# charger_v4.net
KiCad netlist of a schematic drawn in EAGLE
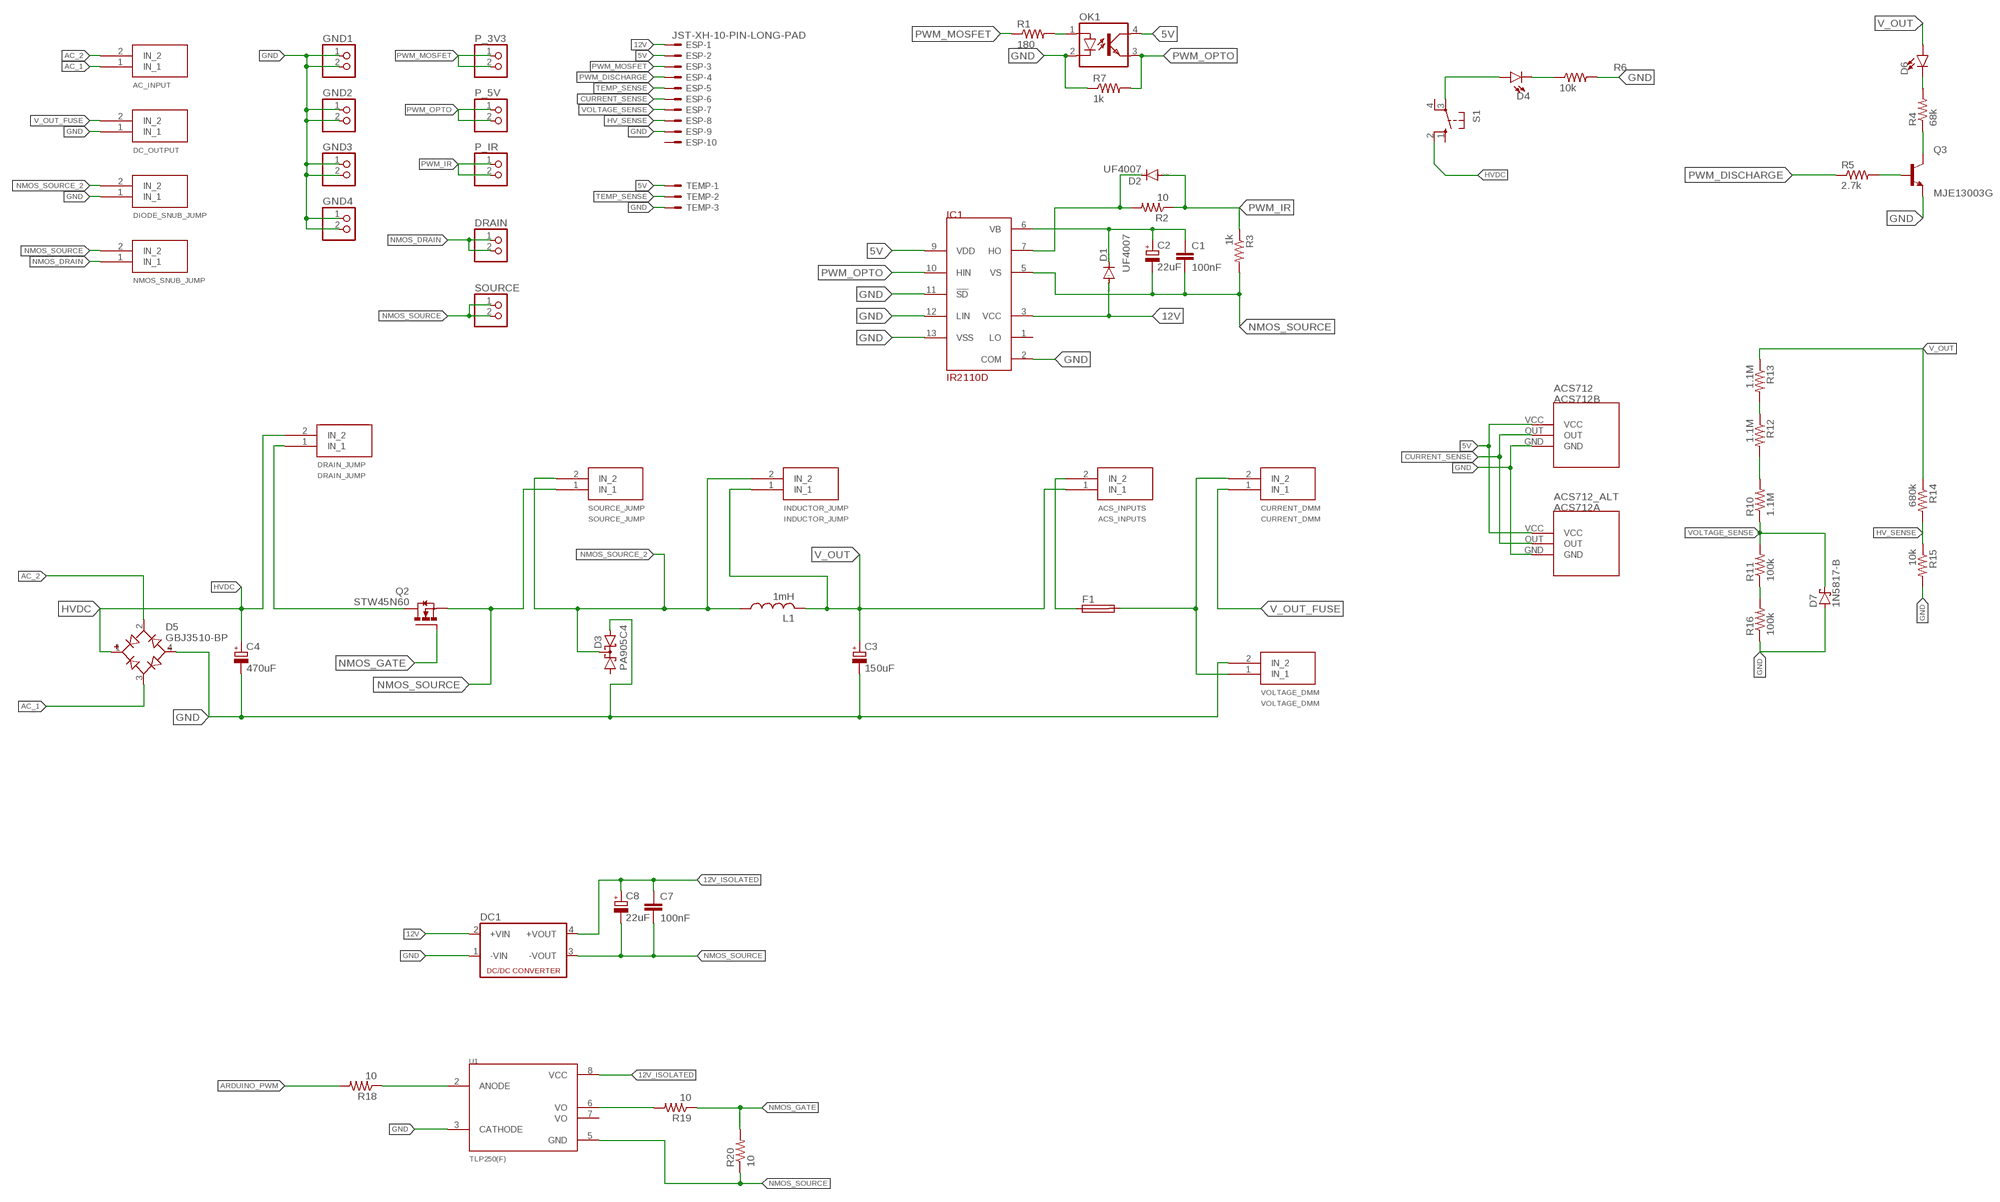
[diagram p0: schematic, sheet 1]

(export (version "E")
  (design (tool "Eeschema 10.0.6"))
  (components
    (comp (ref "ACS712")
      (value "ACS712B")
      (footprint "eagle-import:ACS712-2")
      (libsource (lib "eagle-import") (part "ACS712B"))
    )
    (comp (ref "ACS712_ALT")
      (value "ACS712A")
      (footprint "eagle-import:ACS712-1")
      (libsource (lib "eagle-import") (part "ACS712A"))
    )
    (comp (ref "ACS_INPUTS")
      (value "ACS_INPUTS")
      (footprint "eagle-import:TERMINAL_2P")
      (libsource (lib "eagle-import") (part "TERMINAL_2P"))
    )
    (comp (ref "AC_INPUT")
      (value "AC_INPUT")
      (footprint "eagle-import:TERMINAL_2P")
      (libsource (lib "eagle-import") (part "TERMINAL_2P"))
    )
    (comp (ref "C1")
      (value "100nF")
      (footprint "eagle-import:C025-025X050")
      (libsource (lib "eagle-import") (part "C-EU025-025X050"))
    )
    (comp (ref "C2")
      (value "22uF")
      (footprint "eagle-import:E2,5-6E")
      (libsource (lib "eagle-import") (part "CPOL-EUE2,5-6E"))
    )
    (comp (ref "C3")
      (value "150uF")
      (footprint "eagle-import:E7,5-18")
      (libsource (lib "eagle-import") (part "CPOL-EUE7.5-18"))
    )
    (comp (ref "C4")
      (value "470uF")
      (footprint "eagle-import:EB35D")
      (libsource (lib "eagle-import") (part "CPOL-EUE10-35"))
    )
    (comp (ref "C7")
      (value "100nF")
      (footprint "eagle-import:C025-025X050")
      (libsource (lib "eagle-import") (part "C-EU025-025X050"))
    )
    (comp (ref "C8")
      (value "22uF")
      (footprint "eagle-import:E2,5-6E")
      (libsource (lib "eagle-import") (part "CPOL-EUE2,5-6E"))
    )
    (comp (ref "CURRENT_DMM")
      (value "CURRENT_DMM")
      (footprint "eagle-import:TERMINAL_2P")
      (libsource (lib "eagle-import") (part "TERMINAL_2P"))
    )
    (comp (ref "D1")
      (value "UF4007")
      (footprint "eagle-import:DO34-7")
      (libsource (lib "eagle-import") (part "BAS15"))
    )
    (comp (ref "D2")
      (value "UF4007")
      (footprint "eagle-import:DO34-7")
      (libsource (lib "eagle-import") (part "BAS15"))
    )
    (comp (ref "D3")
      (value "PA905C4")
      (footprint "eagle-import:SOT93S")
      (libsource (lib "eagle-import") (part "PBYR3035"))
    )
    (comp (ref "D4")
      (value "LED5MM")
      (footprint "eagle-import:LED_5MM")
      (libsource (lib "eagle-import") (part "LED5MM"))
    )
    (comp (ref "D5")
      (value "GBJ3510-BP")
      (footprint "eagle-import:DIOB_GBJ3510-BP")
      (fields (field (name "MF") "Micro Commercial"))
      (libsource (lib "eagle-import") (part "GBJ3510-BP"))
    )
    (comp (ref "D6")
      (value "LED5MM")
      (footprint "eagle-import:LED_5MM")
      (libsource (lib "eagle-import") (part "LED5MM"))
    )
    (comp (ref "D7")
      (value "1N5817-B")
      (footprint "eagle-import:DO41-7.6")
      (libsource (lib "eagle-import") (part "1N5817-B"))
    )
    (comp (ref "DC1")
      (value "NME")
      (footprint "eagle-import:NME")
      (fields (field (name "MF") "C & D TECHNOLOGIES, INC") (field (name "MPN") "NME1205D"))
      (libsource (lib "eagle-import") (part "NME"))
    )
    (comp (ref "DC_OUTPUT")
      (value "DC_OUTPUT")
      (footprint "eagle-import:TERMINAL_2P")
      (libsource (lib "eagle-import") (part "TERMINAL_2P"))
    )
    (comp (ref "DIODE_SNUB_JUMP")
      (value "DIODE_SNUB_JUMP")
      (footprint "eagle-import:TERMINAL_2P")
      (libsource (lib "eagle-import") (part "TERMINAL_2P"))
    )
    (comp (ref "DRAIN")
      (value "PINHD-1X2")
      (footprint "eagle-import:1X02")
      (libsource (lib "eagle-import") (part "PINHD-1X2"))
    )
    (comp (ref "DRAIN_JUMP")
      (value "DRAIN_JUMP")
      (footprint "eagle-import:TERMINAL_2P")
      (libsource (lib "eagle-import") (part "TERMINAL_2P"))
    )
    (comp (ref "ESP")
      (value "JST-XH-10-PIN-LONG-PAD")
      (footprint "eagle-import:JST-XH-10-PACKAGE-LONG-PAD")
      (libsource (lib "eagle-import") (part "JST-XH-10-PIN-LONG-PAD"))
    )
    (comp (ref "F1")
      (value "FUSEHOLDER")
      (footprint "eagle-import:FUSEHOLDER")
      (fields (field (name "MPN") "0031.7701.11"))
      (libsource (lib "eagle-import") (part "FUSEHOLDER"))
    )
    (comp (ref "GND1")
      (value "PINHD-1X2")
      (footprint "eagle-import:1X02")
      (libsource (lib "eagle-import") (part "PINHD-1X2"))
    )
    (comp (ref "GND2")
      (value "PINHD-1X2")
      (footprint "eagle-import:1X02")
      (libsource (lib "eagle-import") (part "PINHD-1X2"))
    )
    (comp (ref "GND3")
      (value "PINHD-1X2")
      (footprint "eagle-import:1X02")
      (libsource (lib "eagle-import") (part "PINHD-1X2"))
    )
    (comp (ref "GND4")
      (value "PINHD-1X2")
      (footprint "eagle-import:1X02")
      (libsource (lib "eagle-import") (part "PINHD-1X2"))
    )
    (comp (ref "IC1")
      (value "IR2110D")
      (footprint "eagle-import:DIL14")
      (libsource (lib "eagle-import") (part "IR2110D"))
    )
    (comp (ref "INDUCTOR_JUMP")
      (value "INDUCTOR_JUMP")
      (footprint "eagle-import:TERMINAL_2P")
      (libsource (lib "eagle-import") (part "TERMINAL_2P"))
    )
    (comp (ref "L1")
      (value "1mH")
      (footprint "eagle-import:TJ7-U1")
      (libsource (lib "eagle-import") (part "L-USTJ7-U1"))
    )
    (comp (ref "NMOS_SNUB_JUMP")
      (value "NMOS_SNUB_JUMP")
      (footprint "eagle-import:TERMINAL_2P")
      (libsource (lib "eagle-import") (part "TERMINAL_2P"))
    )
    (comp (ref "OK1")
      (value "SFH618A-5")
      (footprint "eagle-import:DIP4")
      (fields (field (name "MF") "VISHAY/TELEFUNKEN"))
      (libsource (lib "eagle-import") (part "SFH618?A-5"))
    )
    (comp (ref "P_3V3")
      (value "PINHD-1X2")
      (footprint "eagle-import:1X02")
      (libsource (lib "eagle-import") (part "PINHD-1X2"))
    )
    (comp (ref "P_5V")
      (value "PINHD-1X2")
      (footprint "eagle-import:1X02")
      (libsource (lib "eagle-import") (part "PINHD-1X2"))
    )
    (comp (ref "P_IR")
      (value "PINHD-1X2")
      (footprint "eagle-import:1X02")
      (libsource (lib "eagle-import") (part "PINHD-1X2"))
    )
    (comp (ref "Q2")
      (value "STW45N60")
      (footprint "eagle-import:TO247AC")
      (fields (field (name "MF") "Vishay Siliconix") (field (name "MP") "IRFP240"))
      (libsource (lib "eagle-import") (part "IRFP240"))
    )
    (comp (ref "Q3")
      (value "MJE13003G")
      (footprint "eagle-import:TO229P780X300X1364-3")
      (fields (field (name "MF") "ON Semiconductor"))
      (libsource (lib "eagle-import") (part "MJE13003G"))
    )
    (comp (ref "R1")
      (value "180")
      (footprint "eagle-import:0204_7")
      (libsource (lib "eagle-import") (part "R-US_0204/7"))
    )
    (comp (ref "R2")
      (value "10")
      (footprint "eagle-import:0204_7")
      (libsource (lib "eagle-import") (part "R-US_0204/7"))
    )
    (comp (ref "R3")
      (value "1k")
      (footprint "eagle-import:0204_7")
      (libsource (lib "eagle-import") (part "R-US_0204/7"))
    )
    (comp (ref "R4")
      (value "68k")
      (footprint "eagle-import:0411_15")
      (libsource (lib "eagle-import") (part "R-US_0411/15"))
    )
    (comp (ref "R5")
      (value "2.7k")
      (footprint "eagle-import:0204_7")
      (libsource (lib "eagle-import") (part "R-US_0204/7"))
    )
    (comp (ref "R6")
      (value "10k")
      (footprint "eagle-import:0204_7")
      (libsource (lib "eagle-import") (part "R-US_0204/7"))
    )
    (comp (ref "R7")
      (value "1k")
      (footprint "eagle-import:0204_7")
      (libsource (lib "eagle-import") (part "R-US_0204/7"))
    )
    (comp (ref "R10")
      (value "1.1M")
      (footprint "eagle-import:R0805")
      (libsource (lib "eagle-import") (part "R-US_R0805"))
    )
    (comp (ref "R11")
      (value "100k")
      (footprint "eagle-import:R0805")
      (libsource (lib "eagle-import") (part "R-US_R0805"))
    )
    (comp (ref "R12")
      (value "1.1M")
      (footprint "eagle-import:R0805")
      (libsource (lib "eagle-import") (part "R-US_R0805"))
    )
    (comp (ref "R13")
      (value "1.1M")
      (footprint "eagle-import:R0805")
      (libsource (lib "eagle-import") (part "R-US_R0805"))
    )
    (comp (ref "R14")
      (value "680k")
      (footprint "eagle-import:0207_10")
      (libsource (lib "eagle-import") (part "R-US_0207/10"))
    )
    (comp (ref "R15")
      (value "10k")
      (footprint "eagle-import:0207_10")
      (libsource (lib "eagle-import") (part "R-US_0207/10"))
    )
    (comp (ref "R16")
      (value "100k")
      (footprint "eagle-import:R0805")
      (libsource (lib "eagle-import") (part "R-US_R0805"))
    )
    (comp (ref "R18")
      (value "10")
      (footprint "eagle-import:0204_7")
      (libsource (lib "eagle-import") (part "R-US_0204/7"))
    )
    (comp (ref "R19")
      (value "10")
      (footprint "eagle-import:0204_7")
      (libsource (lib "eagle-import") (part "R-US_0204/7"))
    )
    (comp (ref "R20")
      (value "10")
      (footprint "eagle-import:0204_7")
      (libsource (lib "eagle-import") (part "R-US_0204/7"))
    )
    (comp (ref "S1")
      (value "10-XX")
      (footprint "eagle-import:B3F-10XX")
      (fields (field (name "MPN") "B3F-1000"))
      (libsource (lib "eagle-import") (part "10-XX"))
    )
    (comp (ref "SOURCE")
      (value "PINHD-1X2")
      (footprint "eagle-import:1X02")
      (libsource (lib "eagle-import") (part "PINHD-1X2"))
    )
    (comp (ref "SOURCE_JUMP")
      (value "SOURCE_JUMP")
      (footprint "eagle-import:TERMINAL_2P")
      (libsource (lib "eagle-import") (part "TERMINAL_2P"))
    )
    (comp (ref "TEMP")
      (value "JST-XH-03-PIN-LONG-PAD")
      (footprint "eagle-import:JST-XH-03-PACKAGE-LONG-PAD")
      (libsource (lib "eagle-import") (part "JST-XH-03-PIN-LONG-PAD"))
    )
    (comp (ref "U1")
      (value "TLP250(F)")
      (footprint "eagle-import:DIP1016W50P254L966H380Q8P")
      (fields (field (name "MF") "Toshiba"))
      (libsource (lib "eagle-import") (part "TLP250(F)"))
    )
    (comp (ref "VOLTAGE_DMM")
      (value "VOLTAGE_DMM")
      (footprint "eagle-import:TERMINAL_2P")
      (libsource (lib "eagle-import") (part "TERMINAL_2P"))
    )
  )
  (nets
    (net (code "1") (name "5V") (class "Default")
      (node (ref "ACS712") (pin "VCC") (pinfunction "VCC_VCC") (pintype "bidirectional"))
      (node (ref "ACS712_ALT") (pin "VCC") (pinfunction "VCC_VCC") (pintype "bidirectional"))
      (node (ref "ESP") (pin "2") (pinfunction "S_2") (pintype "passive"))
      (node (ref "IC1") (pin "9") (pinfunction "VDD_9") (pintype "power_in"))
      (node (ref "OK1") (pin "4") (pinfunction "COL_4") (pintype "passive"))
      (node (ref "TEMP") (pin "1") (pinfunction "S_1") (pintype "passive"))
    )
    (net (code "2") (name "12V") (class "Default")
      (node (ref "D1") (pin "A") (pinfunction "A_A") (pintype "passive"))
      (node (ref "DC1") (pin "2") (pinfunction "+VIN_2") (pintype "passive"))
      (node (ref "ESP") (pin "1") (pinfunction "S_1") (pintype "passive"))
      (node (ref "IC1") (pin "3") (pinfunction "VCC_3") (pintype "power_in"))
    )
    (net (code "3") (name "12V_ISOLATED") (class "Default")
      (node (ref "C7") (pin "1") (pinfunction "1_1") (pintype "passive"))
      (node (ref "C8") (pin "+") (pinfunction "+_+") (pintype "passive"))
      (node (ref "DC1") (pin "4") (pinfunction "+VOUT_4") (pintype "passive"))
      (node (ref "U1") (pin "8") (pinfunction "VCC_8") (pintype "power_in"))
    )
    (net (code "4") (name "AC_1") (class "Default")
      (node (ref "AC_INPUT") (pin "1") (pinfunction "IN_1_1") (pintype "bidirectional"))
      (node (ref "D5") (pin "3") (pinfunction "AC2_3") (pintype "passive"))
    )
    (net (code "5") (name "AC_2") (class "Default")
      (node (ref "AC_INPUT") (pin "2") (pinfunction "IN_2_2") (pintype "bidirectional"))
      (node (ref "D5") (pin "2") (pinfunction "AC1_2") (pintype "passive"))
    )
    (net (code "6") (name "ARDUINO_PWM") (class "Default")
      (node (ref "R18") (pin "2") (pinfunction "2_2") (pintype "passive"))
    )
    (net (code "7") (name "CURRENT_SENSE") (class "Default")
      (node (ref "ACS712") (pin "OUT") (pinfunction "OUT_OUT") (pintype "bidirectional"))
      (node (ref "ACS712_ALT") (pin "OUT") (pinfunction "OUT_OUT") (pintype "bidirectional"))
      (node (ref "ESP") (pin "6") (pinfunction "S_6") (pintype "passive"))
    )
    (net (code "8") (name "GND") (class "Default")
      (node (ref "ACS712") (pin "GND") (pinfunction "GND_GND") (pintype "bidirectional"))
      (node (ref "ACS712_ALT") (pin "GND") (pinfunction "GND_GND") (pintype "bidirectional"))
      (node (ref "C3") (pin "-") (pinfunction "-_-") (pintype "passive"))
      (node (ref "C4") (pin "-") (pinfunction "-_-") (pintype "passive"))
      (node (ref "D3") (pin "A2") (pinfunction "A2_A2") (pintype "passive"))
      (node (ref "D5") (pin "4") (pinfunction "-_4") (pintype "passive"))
      (node (ref "D7") (pin "A") (pinfunction "A_A") (pintype "passive"))
      (node (ref "DC1") (pin "1") (pinfunction "-VIN_1") (pintype "passive"))
      (node (ref "DC_OUTPUT") (pin "1") (pinfunction "IN_1_1") (pintype "bidirectional"))
      (node (ref "DIODE_SNUB_JUMP") (pin "1") (pinfunction "IN_1_1") (pintype "bidirectional"))
      (node (ref "ESP") (pin "9") (pinfunction "S_9") (pintype "passive"))
      (node (ref "GND1") (pin "1") (pinfunction "1_1") (pintype "passive"))
      (node (ref "GND1") (pin "2") (pinfunction "2_2") (pintype "passive"))
      (node (ref "GND2") (pin "1") (pinfunction "1_1") (pintype "passive"))
      (node (ref "GND2") (pin "2") (pinfunction "2_2") (pintype "passive"))
      (node (ref "GND3") (pin "1") (pinfunction "1_1") (pintype "passive"))
      (node (ref "GND3") (pin "2") (pinfunction "2_2") (pintype "passive"))
      (node (ref "GND4") (pin "1") (pinfunction "1_1") (pintype "passive"))
      (node (ref "GND4") (pin "2") (pinfunction "2_2") (pintype "passive"))
      (node (ref "IC1") (pin "11") (pinfunction "~{SD}_11") (pintype "input"))
      (node (ref "IC1") (pin "12") (pinfunction "LIN_12") (pintype "input"))
      (node (ref "IC1") (pin "13") (pinfunction "VSS_13") (pintype "power_in"))
      (node (ref "IC1") (pin "2") (pinfunction "COM_2") (pintype "power_in"))
      (node (ref "OK1") (pin "2") (pinfunction "C_2") (pintype "passive"))
      (node (ref "Q3") (pin "3") (pinfunction "E_3") (pintype "passive"))
      (node (ref "R15") (pin "2") (pinfunction "2_2") (pintype "passive"))
      (node (ref "R16") (pin "1") (pinfunction "1_1") (pintype "passive"))
      (node (ref "R6") (pin "2") (pinfunction "2_2") (pintype "passive"))
      (node (ref "R7") (pin "1") (pinfunction "1_1") (pintype "passive"))
      (node (ref "TEMP") (pin "3") (pinfunction "S_3") (pintype "passive"))
      (node (ref "U1") (pin "3") (pinfunction "CATHODE_3") (pintype "passive"))
      (node (ref "VOLTAGE_DMM") (pin "2") (pinfunction "IN_2_2") (pintype "bidirectional"))
    )
    (net (code "9") (name "HVDC") (class "Default")
      (node (ref "C4") (pin "+") (pinfunction "+_+") (pintype "passive"))
      (node (ref "D5") (pin "1") (pinfunction "+_1") (pintype "passive"))
      (node (ref "DRAIN_JUMP") (pin "2") (pinfunction "IN_2_2") (pintype "bidirectional"))
      (node (ref "S1") (pin "2") (pinfunction "S1_2") (pintype "passive"))
    )
    (net (code "10") (name "HV_SENSE") (class "Default")
      (node (ref "ESP") (pin "8") (pinfunction "S_8") (pintype "passive"))
      (node (ref "R14") (pin "2") (pinfunction "2_2") (pintype "passive"))
      (node (ref "R15") (pin "1") (pinfunction "1_1") (pintype "passive"))
    )
    (net (code "11") (name "NMOS_DRAIN") (class "Default")
      (node (ref "DRAIN") (pin "1") (pinfunction "1_1") (pintype "passive"))
      (node (ref "DRAIN") (pin "2") (pinfunction "2_2") (pintype "passive"))
      (node (ref "DRAIN_JUMP") (pin "1") (pinfunction "IN_1_1") (pintype "bidirectional"))
      (node (ref "NMOS_SNUB_JUMP") (pin "1") (pinfunction "IN_1_1") (pintype "bidirectional"))
      (node (ref "Q2") (pin "2") (pinfunction "D_2") (pintype "passive"))
    )
    (net (code "12") (name "NMOS_GATE") (class "Default")
      (node (ref "Q2") (pin "1") (pinfunction "G_1") (pintype "passive"))
      (node (ref "R19") (pin "1") (pinfunction "1_1") (pintype "passive"))
      (node (ref "R20") (pin "2") (pinfunction "2_2") (pintype "passive"))
    )
    (net (code "13") (name "NMOS_SOURCE") (class "Default")
      (node (ref "C1") (pin "2") (pinfunction "2_2") (pintype "passive"))
      (node (ref "C2") (pin "-") (pinfunction "-_-") (pintype "passive"))
      (node (ref "C7") (pin "2") (pinfunction "2_2") (pintype "passive"))
      (node (ref "C8") (pin "-") (pinfunction "-_-") (pintype "passive"))
      (node (ref "DC1") (pin "3") (pinfunction "-VOUT_3") (pintype "passive"))
      (node (ref "IC1") (pin "5") (pinfunction "VS_5") (pintype "power_in"))
      (node (ref "NMOS_SNUB_JUMP") (pin "2") (pinfunction "IN_2_2") (pintype "bidirectional"))
      (node (ref "Q2") (pin "3") (pinfunction "S_3") (pintype "passive"))
      (node (ref "R20") (pin "1") (pinfunction "1_1") (pintype "passive"))
      (node (ref "R3") (pin "2") (pinfunction "2_2") (pintype "passive"))
      (node (ref "SOURCE") (pin "1") (pinfunction "1_1") (pintype "passive"))
      (node (ref "SOURCE") (pin "2") (pinfunction "2_2") (pintype "passive"))
      (node (ref "SOURCE_JUMP") (pin "1") (pinfunction "IN_1_1") (pintype "bidirectional"))
      (node (ref "U1") (pin "5") (pinfunction "GND_5") (pintype "power_in"))
    )
    (net (code "14") (name "NMOS_SOURCE_2") (class "Default")
      (node (ref "D3") (pin "C") (pinfunction "C_C") (pintype "passive"))
      (node (ref "DIODE_SNUB_JUMP") (pin "2") (pinfunction "IN_2_2") (pintype "bidirectional"))
      (node (ref "INDUCTOR_JUMP") (pin "2") (pinfunction "IN_2_2") (pintype "bidirectional"))
      (node (ref "L1") (pin "1") (pinfunction "1_1") (pintype "passive"))
      (node (ref "SOURCE_JUMP") (pin "2") (pinfunction "IN_2_2") (pintype "bidirectional"))
    )
    (net (code "15") (name "Net-(ACS_INPUTS-IN_2)") (class "Default")
      (node (ref "ACS_INPUTS") (pin "2") (pinfunction "IN_2_2") (pintype "bidirectional"))
      (node (ref "F1") (pin "1") (pinfunction "1_1") (pintype "passive"))
    )
    (net (code "16") (name "Net-(CURRENT_DMM-IN_2)") (class "Default")
      (node (ref "CURRENT_DMM") (pin "2") (pinfunction "IN_2_2") (pintype "bidirectional"))
      (node (ref "F1") (pin "2") (pinfunction "2_2") (pintype "passive"))
      (node (ref "VOLTAGE_DMM") (pin "1") (pinfunction "IN_1_1") (pintype "bidirectional"))
    )
    (net (code "17") (name "Net-(D4-C)") (class "Default")
      (node (ref "D4") (pin "K") (pinfunction "C_K") (pintype "passive"))
      (node (ref "R6") (pin "1") (pinfunction "1_1") (pintype "passive"))
    )
    (net (code "18") (name "Net-(D6-C)") (class "Default")
      (node (ref "D6") (pin "K") (pinfunction "C_K") (pintype "passive"))
      (node (ref "R4") (pin "2") (pinfunction "2_2") (pintype "passive"))
    )
    (net (code "19") (name "Net-(IC1-HO)") (class "Default")
      (node (ref "D2") (pin "C") (pinfunction "C_C") (pintype "passive"))
      (node (ref "IC1") (pin "7") (pinfunction "HO_7") (pintype "output"))
      (node (ref "R2") (pin "2") (pinfunction "2_2") (pintype "passive"))
    )
    (net (code "20") (name "Net-(IC1-VB)") (class "Default")
      (node (ref "C1") (pin "1") (pinfunction "1_1") (pintype "passive"))
      (node (ref "C2") (pin "+") (pinfunction "+_+") (pintype "passive"))
      (node (ref "D1") (pin "C") (pinfunction "C_C") (pintype "passive"))
      (node (ref "IC1") (pin "6") (pinfunction "VB_6") (pintype "power_in"))
    )
    (net (code "21") (name "Net-(OK1-A)") (class "Default")
      (node (ref "OK1") (pin "1") (pinfunction "A_1") (pintype "passive"))
      (node (ref "R1") (pin "2") (pinfunction "2_2") (pintype "passive"))
    )
    (net (code "22") (name "Net-(Q3-B)") (class "Default")
      (node (ref "Q3") (pin "1") (pinfunction "B_1") (pintype "passive"))
      (node (ref "R5") (pin "2") (pinfunction "2_2") (pintype "passive"))
    )
    (net (code "23") (name "Net-(Q3-C)") (class "Default")
      (node (ref "Q3") (pin "2") (pinfunction "C_2") (pintype "passive"))
      (node (ref "R4") (pin "1") (pinfunction "1_1") (pintype "passive"))
    )
    (net (code "24") (name "Net-(R10-Pad2)") (class "Default")
      (node (ref "R10") (pin "2") (pinfunction "2_2") (pintype "passive"))
      (node (ref "R12") (pin "2") (pinfunction "2_2") (pintype "passive"))
    )
    (net (code "25") (name "Net-(R11-Pad1)") (class "Default")
      (node (ref "R11") (pin "1") (pinfunction "1_1") (pintype "passive"))
      (node (ref "R16") (pin "2") (pinfunction "2_2") (pintype "passive"))
    )
    (net (code "26") (name "Net-(R12-Pad1)") (class "Default")
      (node (ref "R12") (pin "1") (pinfunction "1_1") (pintype "passive"))
      (node (ref "R13") (pin "2") (pinfunction "2_2") (pintype "passive"))
    )
    (net (code "27") (name "Net-(R19-Pad2)") (class "Default")
      (node (ref "R19") (pin "2") (pinfunction "2_2") (pintype "passive"))
      (node (ref "U1") (pin "6") (pinfunction "VO_6") (pintype "output"))
    )
    (net (code "28") (name "Net-(S1-P)") (class "Default")
      (node (ref "D4") (pin "A") (pinfunction "A_A") (pintype "passive"))
      (node (ref "S1") (pin "3") (pinfunction "P_3") (pintype "passive"))
    )
    (net (code "29") (name "Net-(U1-ANODE)") (class "Default")
      (node (ref "R18") (pin "1") (pinfunction "1_1") (pintype "passive"))
      (node (ref "U1") (pin "2") (pinfunction "ANODE_2") (pintype "passive"))
    )
    (net (code "30") (name "PWM_DISCHARGE") (class "Default")
      (node (ref "ESP") (pin "4") (pinfunction "S_4") (pintype "passive"))
      (node (ref "R5") (pin "1") (pinfunction "1_1") (pintype "passive"))
    )
    (net (code "31") (name "PWM_IR") (class "Default")
      (node (ref "D2") (pin "A") (pinfunction "A_A") (pintype "passive"))
      (node (ref "P_IR") (pin "1") (pinfunction "1_1") (pintype "passive"))
      (node (ref "P_IR") (pin "2") (pinfunction "2_2") (pintype "passive"))
      (node (ref "R2") (pin "1") (pinfunction "1_1") (pintype "passive"))
      (node (ref "R3") (pin "1") (pinfunction "1_1") (pintype "passive"))
    )
    (net (code "32") (name "PWM_MOSFET") (class "Default")
      (node (ref "ESP") (pin "3") (pinfunction "S_3") (pintype "passive"))
      (node (ref "P_3V3") (pin "1") (pinfunction "1_1") (pintype "passive"))
      (node (ref "P_3V3") (pin "2") (pinfunction "2_2") (pintype "passive"))
      (node (ref "R1") (pin "1") (pinfunction "1_1") (pintype "passive"))
    )
    (net (code "33") (name "PWM_OPTO") (class "Default")
      (node (ref "IC1") (pin "10") (pinfunction "HIN_10") (pintype "input"))
      (node (ref "OK1") (pin "3") (pinfunction "EMIT_3") (pintype "passive"))
      (node (ref "P_5V") (pin "1") (pinfunction "1_1") (pintype "passive"))
      (node (ref "P_5V") (pin "2") (pinfunction "2_2") (pintype "passive"))
      (node (ref "R7") (pin "2") (pinfunction "2_2") (pintype "passive"))
    )
    (net (code "34") (name "TEMP_SENSE") (class "Default")
      (node (ref "ESP") (pin "5") (pinfunction "S_5") (pintype "passive"))
      (node (ref "TEMP") (pin "2") (pinfunction "S_2") (pintype "passive"))
    )
    (net (code "35") (name "VOLTAGE_SENSE") (class "Default")
      (node (ref "D7") (pin "C") (pinfunction "C_C") (pintype "passive"))
      (node (ref "ESP") (pin "7") (pinfunction "S_7") (pintype "passive"))
      (node (ref "R10") (pin "1") (pinfunction "1_1") (pintype "passive"))
      (node (ref "R11") (pin "2") (pinfunction "2_2") (pintype "passive"))
    )
    (net (code "36") (name "V_OUT") (class "Default")
      (node (ref "ACS_INPUTS") (pin "1") (pinfunction "IN_1_1") (pintype "bidirectional"))
      (node (ref "C3") (pin "+") (pinfunction "+_+") (pintype "passive"))
      (node (ref "D6") (pin "A") (pinfunction "A_A") (pintype "passive"))
      (node (ref "INDUCTOR_JUMP") (pin "1") (pinfunction "IN_1_1") (pintype "bidirectional"))
      (node (ref "L1") (pin "2") (pinfunction "2_2") (pintype "passive"))
      (node (ref "R13") (pin "1") (pinfunction "1_1") (pintype "passive"))
      (node (ref "R14") (pin "1") (pinfunction "1_1") (pintype "passive"))
    )
    (net (code "37") (name "V_OUT_FUSE") (class "Default")
      (node (ref "CURRENT_DMM") (pin "1") (pinfunction "IN_1_1") (pintype "bidirectional"))
      (node (ref "DC_OUTPUT") (pin "2") (pinfunction "IN_2_2") (pintype "bidirectional"))
    )
    (net (code "38") (name "unconnected-(D3-PadA1)") (class "Default")
      (node (ref "D3") (pin "A1") (pinfunction "A1_A1") (pintype "passive"))
    )
    (net (code "39") (name "unconnected-(ESPB-S-Pad10)") (class "Default")
      (node (ref "ESP") (pin "10") (pinfunction "S_10") (pintype "passive"))
    )
    (net (code "40") (name "unconnected-(IC1-LO-Pad1)") (class "Default")
      (node (ref "IC1") (pin "1") (pinfunction "LO_1") (pintype "output"))
    )
    (net (code "41") (name "unconnected-(S1-P1-Pad4)") (class "Default")
      (node (ref "S1") (pin "4") (pinfunction "P1_4") (pintype "passive"))
    )
    (net (code "42") (name "unconnected-(S1-S-Pad1)") (class "Default")
      (node (ref "S1") (pin "1") (pinfunction "S_1") (pintype "passive"))
    )
    (net (code "43") (name "unconnected-(U1-VO-Pad7)") (class "Default")
      (node (ref "U1") (pin "7") (pinfunction "VO_7") (pintype "output"))
    )
  )
)
